# SecondStageAmplifier.net
KiCad netlist of a schematic drawn in Altium Designer
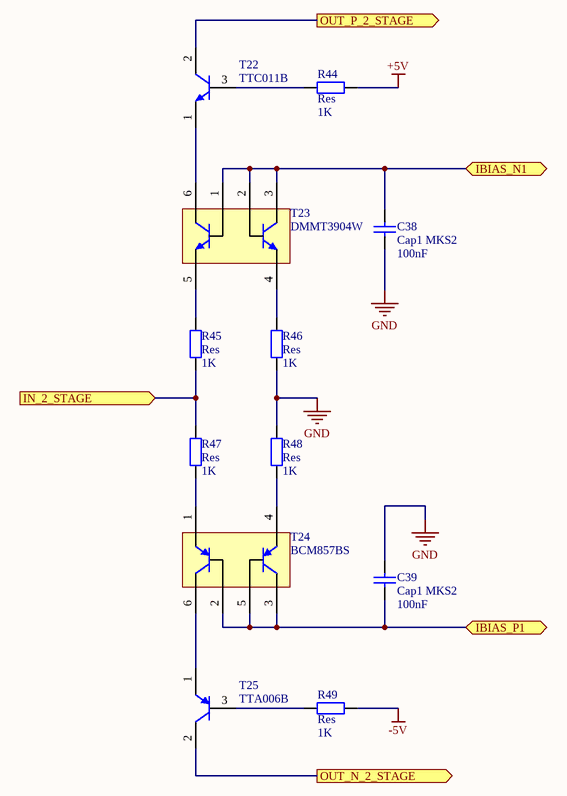
[diagram p0: SecondStageAmplifier.SchDoc]

(export (version "E")
  (design (tool "Eeschema 10.0.6"))
  (components
    (comp (ref "C38")
      (value "Cap1 MKS2")
      (footprint "CAP-0.5-WIMA_MKS2")
      (description "WIMA MKS2 Metallized Polyester (PET) \r\nCapacitors in PCM 5 mm")
      (fields (field (name "ALTIUM_VALUE") "100nF"))
      (libsource (lib "SchematicLib") (part "Cap1"))
    )
    (comp (ref "C39")
      (value "Cap1 MKS2")
      (footprint "CAP-0.5-WIMA_MKS2")
      (description "WIMA MKS2 Metallized Polyester (PET) \r\nCapacitors in PCM 5 mm")
      (fields (field (name "ALTIUM_VALUE") "100nF"))
      (libsource (lib "SchematicLib") (part "Cap1"))
    )
    (comp (ref "R44")
      (value "Res")
      (footprint "RESISTOR-10mm")
      (description "Resistor")
      (fields (field (name "ALTIUM_VALUE") "1K"))
      (libsource (lib "") (part "Res_1"))
    )
    (comp (ref "R45")
      (value "Res")
      (footprint "RESISTOR-10mm")
      (description "Resistor")
      (fields (field (name "ALTIUM_VALUE") "1K"))
      (libsource (lib "SchematicLib") (part "Res"))
    )
    (comp (ref "R46")
      (value "Res")
      (footprint "RESISTOR-10mm")
      (description "Resistor")
      (fields (field (name "ALTIUM_VALUE") "1K"))
      (libsource (lib "SchematicLib") (part "Res"))
    )
    (comp (ref "R47")
      (value "Res")
      (footprint "RESISTOR-10mm")
      (description "Resistor")
      (fields (field (name "ALTIUM_VALUE") "1K"))
      (libsource (lib "SchematicLib") (part "Res"))
    )
    (comp (ref "R48")
      (value "Res")
      (footprint "RESISTOR-10mm")
      (description "Resistor")
      (fields (field (name "ALTIUM_VALUE") "1K"))
      (libsource (lib "SchematicLib") (part "Res"))
    )
    (comp (ref "R49")
      (value "Res")
      (footprint "RESISTOR-10mm")
      (description "Resistor")
      (fields (field (name "ALTIUM_VALUE") "1K"))
      (libsource (lib "SchematicLib") (part "Res"))
    )
    (comp (ref "T22")
      (value "TTC011B")
      (footprint "TO-126")
      (description "NPN High Voltage Transistor")
      (libsource (lib "SchematicLib") (part "TTC011B"))
    )
    (comp (ref "T23")
      (value "DMMT3904W")
      (footprint "SOT363_IPC_MD")
      (description "40V MATCHED PAIR NPN SMALL SIGNAL TRANSISTOR")
      (libsource (lib "SchematicLib") (part "DMMT3904W"))
    )
    (comp (ref "T24")
      (value "BCM857BS")
      (footprint "SOT363_IPC_MD")
      (description "40V MATCHED PAIR NPN SMALL SIGNAL TRANSISTOR")
      (libsource (lib "SchematicLib") (part "BCM857BS"))
    )
    (comp (ref "T25")
      (value "TTA006B")
      (footprint "TO-126")
      (description "PNP High Voltage Transistor")
      (libsource (lib "SchematicLib") (part "TTA006B"))
    )
  )
  (nets
    (net (code "1") (name "+5V") (class "Default")
      (node (ref "R44") (pin "2") (pinfunction "2_2") (pintype "passive"))
    )
    (net (code "2") (name "-5V") (class "Default")
      (node (ref "R49") (pin "2") (pinfunction "2_2") (pintype "passive"))
    )
    (net (code "3") (name "/IBIAS_N1") (class "Default")
      (node (ref "C38") (pin "2") (pinfunction "2_2") (pintype "passive"))
      (node (ref "T23") (pin "1") (pinfunction "B1_1") (pintype "passive"))
      (node (ref "T23") (pin "2") (pinfunction "B2_2") (pintype "passive"))
      (node (ref "T23") (pin "3") (pinfunction "C2_3") (pintype "passive"))
    )
    (net (code "4") (name "/IBIAS_P1") (class "Default")
      (node (ref "C39") (pin "1") (pinfunction "1_1") (pintype "passive"))
      (node (ref "T24") (pin "2") (pinfunction "B1_2") (pintype "passive"))
      (node (ref "T24") (pin "3") (pinfunction "E2_3") (pintype "passive"))
      (node (ref "T24") (pin "5") (pinfunction "B2_5") (pintype "passive"))
    )
    (net (code "5") (name "/IN_2_STAGE") (class "Default")
      (node (ref "R45") (pin "1") (pinfunction "1_1") (pintype "passive"))
      (node (ref "R47") (pin "2") (pinfunction "2_2") (pintype "passive"))
    )
    (net (code "6") (name "/OUT_N_2_STAGE") (class "Default")
      (node (ref "T25") (pin "2") (pinfunction "C_2") (pintype "passive"))
    )
    (net (code "7") (name "/OUT_P_2_STAGE") (class "Default")
      (node (ref "T22") (pin "2") (pinfunction "C_2") (pintype "passive"))
    )
    (net (code "8") (name "GND") (class "Default")
      (node (ref "C38") (pin "1") (pinfunction "1_1") (pintype "passive"))
      (node (ref "C39") (pin "2") (pinfunction "2_2") (pintype "passive"))
      (node (ref "R46") (pin "1") (pinfunction "1_1") (pintype "passive"))
      (node (ref "R48") (pin "2") (pinfunction "2_2") (pintype "passive"))
    )
    (net (code "9") (name "Net-(T22-B)") (class "Default")
      (node (ref "R44") (pin "1") (pinfunction "1_1") (pintype "passive"))
      (node (ref "T22") (pin "3") (pinfunction "B_3") (pintype "passive"))
    )
    (net (code "10") (name "Net-(T22-E)") (class "Default")
      (node (ref "T22") (pin "1") (pinfunction "E_1") (pintype "passive"))
      (node (ref "T23") (pin "6") (pinfunction "C1_6") (pintype "passive"))
    )
    (net (code "11") (name "Net-(T23-E1)") (class "Default")
      (node (ref "R45") (pin "2") (pinfunction "2_2") (pintype "passive"))
      (node (ref "T23") (pin "5") (pinfunction "E1_5") (pintype "passive"))
    )
    (net (code "12") (name "Net-(T23-E2)") (class "Default")
      (node (ref "R46") (pin "2") (pinfunction "2_2") (pintype "passive"))
      (node (ref "T23") (pin "4") (pinfunction "E2_4") (pintype "passive"))
    )
    (net (code "13") (name "Net-(T24-C1)") (class "Default")
      (node (ref "R47") (pin "1") (pinfunction "1_1") (pintype "passive"))
      (node (ref "T24") (pin "1") (pinfunction "C1_1") (pintype "passive"))
    )
    (net (code "14") (name "Net-(T24-C2)") (class "Default")
      (node (ref "R48") (pin "1") (pinfunction "1_1") (pintype "passive"))
      (node (ref "T24") (pin "4") (pinfunction "C2_4") (pintype "passive"))
    )
    (net (code "15") (name "Net-(T24-E1)") (class "Default")
      (node (ref "T24") (pin "6") (pinfunction "E1_6") (pintype "passive"))
      (node (ref "T25") (pin "1") (pinfunction "E_1") (pintype "passive"))
    )
    (net (code "16") (name "Net-(T25-B)") (class "Default")
      (node (ref "R49") (pin "1") (pinfunction "1_1") (pintype "passive"))
      (node (ref "T25") (pin "3") (pinfunction "B_3") (pintype "passive"))
    )
  )
)
